# eagle2_hotovo.net
KiCad netlist of a schematic drawn in EAGLE
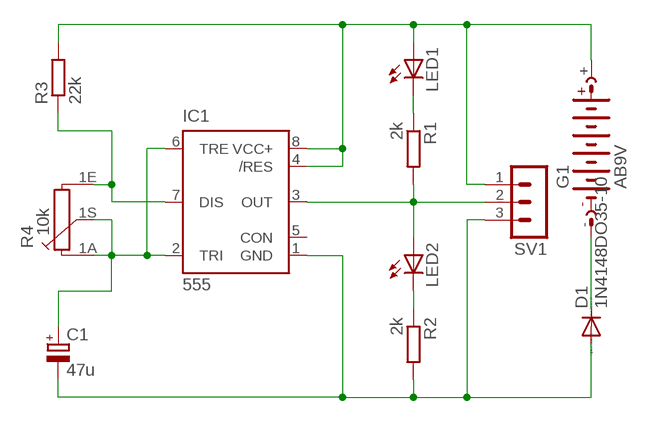
[diagram p0: schematic, sheet 1]

(export (version "E")
  (design (tool "Eeschema 10.0.6"))
  (components
    (comp (ref "C1")
      (value "47u")
      (footprint "eagle-import:E3,5-8")
      (libsource (lib "eagle-import") (part "CPOL-EUE3.5-8"))
    )
    (comp (ref "D1")
      (value "1N4148DO35-10")
      (footprint "eagle-import:DO35-10")
      (libsource (lib "eagle-import") (part "1N4148DO35-10"))
    )
    (comp (ref "G1")
      (value "AB9V")
      (footprint "eagle-import:AB9V")
      (libsource (lib "eagle-import") (part "AB9V"))
    )
    (comp (ref "IC1")
      (value "555")
      (footprint "eagle-import:DIP08")
      (libsource (lib "eagle-import") (part "555P"))
    )
    (comp (ref "LED1")
      (value "LED3MM")
      (footprint "eagle-import:LED3MM")
      (libsource (lib "eagle-import") (part "LED3MM"))
    )
    (comp (ref "LED2")
      (value "LED3MM")
      (footprint "eagle-import:LED3MM")
      (libsource (lib "eagle-import") (part "LED3MM"))
    )
    (comp (ref "R1")
      (value "2k")
      (footprint "eagle-import:0207_10")
      (libsource (lib "eagle-import") (part "R-EU_0207/10"))
    )
    (comp (ref "R2")
      (value "2k")
      (footprint "eagle-import:0207_10")
      (libsource (lib "eagle-import") (part "R-EU_0207/10"))
    )
    (comp (ref "R3")
      (value "22k")
      (footprint "eagle-import:0207_10")
      (libsource (lib "eagle-import") (part "R-EU_0207/10"))
    )
    (comp (ref "R4")
      (value "10k")
      (footprint "eagle-import:PC16S")
      (libsource (lib "eagle-import") (part "PC16S"))
    )
    (comp (ref "SV1")
      (value "MA03-1")
      (footprint "eagle-import:MA03-1")
      (libsource (lib "eagle-import") (part "MA03-1"))
    )
  )
  (nets
    (net (code "1") (name "Net-(D1-PadC)") (class "Default")
      (node (ref "D1") (pin "C") (pinfunction "C_C") (pintype "passive"))
      (node (ref "G1") (pin "-") (pinfunction "-_-") (pintype "passive"))
    )
    (net (code "2") (name "Net-(IC1-DIS)") (class "Default")
      (node (ref "IC1") (pin "7") (pinfunction "DIS_7") (pintype "input"))
      (node (ref "R3") (pin "1") (pinfunction "1_1") (pintype "passive"))
      (node (ref "R4") (pin "1E") (pinfunction "1E_1E") (pintype "passive"))
    )
    (net (code "3") (name "Net-(IC1-GND)") (class "Default")
      (node (ref "C1") (pin "-") (pinfunction "-_-") (pintype "passive"))
      (node (ref "D1") (pin "A") (pinfunction "A_A") (pintype "passive"))
      (node (ref "IC1") (pin "1") (pinfunction "GND_1") (pintype "power_in"))
      (node (ref "R2") (pin "2") (pinfunction "2_2") (pintype "passive"))
      (node (ref "SV1") (pin "3") (pinfunction "3_3") (pintype "passive"))
    )
    (net (code "4") (name "Net-(IC1-OUT)") (class "Default")
      (node (ref "IC1") (pin "3") (pinfunction "OUT_3") (pintype "output"))
      (node (ref "LED2") (pin "A") (pinfunction "A_A") (pintype "passive"))
      (node (ref "R1") (pin "2") (pinfunction "2_2") (pintype "passive"))
      (node (ref "SV1") (pin "2") (pinfunction "2_2") (pintype "passive"))
    )
    (net (code "5") (name "Net-(IC1-TRE)") (class "Default")
      (node (ref "C1") (pin "+") (pinfunction "+_+") (pintype "passive"))
      (node (ref "IC1") (pin "2") (pinfunction "TRI_2") (pintype "input"))
      (node (ref "IC1") (pin "6") (pinfunction "TRE_6") (pintype "input"))
      (node (ref "R4") (pin "1A") (pinfunction "1A_1A") (pintype "passive"))
      (node (ref "R4") (pin "1S") (pinfunction "1S_1S") (pintype "passive"))
    )
    (net (code "6") (name "Net-(IC1-VCC+)") (class "Default")
      (node (ref "G1") (pin "+") (pinfunction "+_+") (pintype "passive"))
      (node (ref "IC1") (pin "4") (pinfunction "/RES_4") (pintype "input"))
      (node (ref "IC1") (pin "8") (pinfunction "VCC+_8") (pintype "power_in"))
      (node (ref "LED1") (pin "A") (pinfunction "A_A") (pintype "passive"))
      (node (ref "R3") (pin "2") (pinfunction "2_2") (pintype "passive"))
      (node (ref "SV1") (pin "1") (pinfunction "1_1") (pintype "passive"))
    )
    (net (code "7") (name "Net-(LED1-C)") (class "Default")
      (node (ref "LED1") (pin "K") (pinfunction "C_K") (pintype "passive"))
      (node (ref "R1") (pin "1") (pinfunction "1_1") (pintype "passive"))
    )
    (net (code "8") (name "Net-(LED2-C)") (class "Default")
      (node (ref "LED2") (pin "K") (pinfunction "C_K") (pintype "passive"))
      (node (ref "R2") (pin "1") (pinfunction "1_1") (pintype "passive"))
    )
    (net (code "9") (name "unconnected-(IC1-CON-Pad5)") (class "Default")
      (node (ref "IC1") (pin "5") (pinfunction "CON_5") (pintype "input"))
    )
  )
)
